# Mechanical.net
KiCad netlist of a schematic drawn in Altium Designer
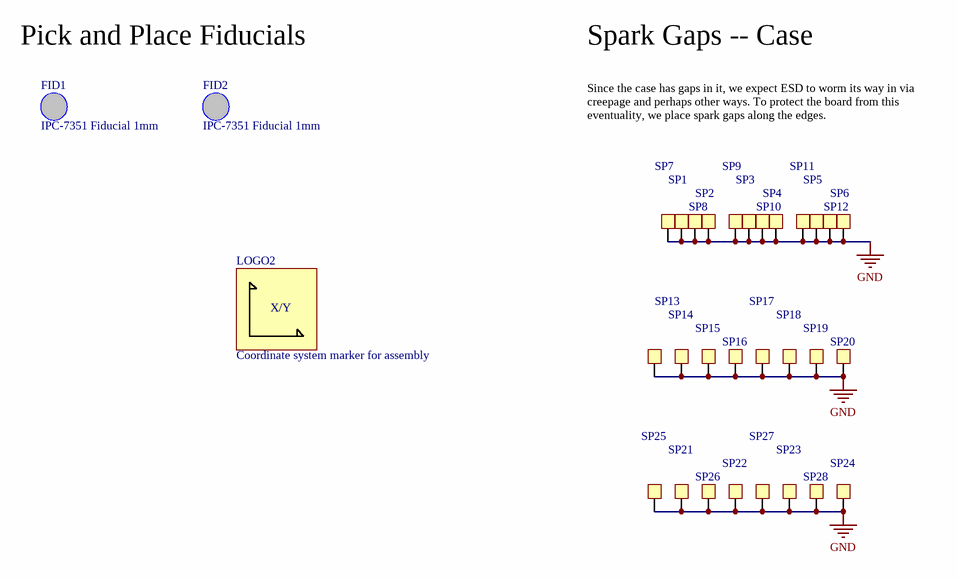
[diagram p0: Mechanical.SchDoc]

(export (version "E")
  (design (tool "Eeschema 10.0.6"))
  (components
    (comp (ref "FID1")
      (value "IPC-7351 Fiducial 1mm")
      (footprint "FIDUCIAL_1.5")
      (libsource (lib "Mechanical") (part "FIDUCIAL_1.5"))
    )
    (comp (ref "FID2")
      (value "IPC-7351 Fiducial 1mm")
      (footprint "FIDUCIAL_1.5")
      (libsource (lib "Mechanical") (part "FIDUCIAL_1.5"))
    )
    (comp (ref "LOGO2")
      (value "Coordinate system marker for assembly")
      (footprint "Coordinate System")
      (libsource (lib "Graphics") (part "CoordinateSystem"))
    )
    (comp (ref "SP1")
      (value "Spark Gap")
      (footprint "SparkGap")
      (description "Open square pad for spark gapping")
      (libsource (lib "PCBFeatures") (part "Spark Gap"))
    )
    (comp (ref "SP2")
      (value "Spark Gap")
      (footprint "SparkGap")
      (description "Open square pad for spark gapping")
      (libsource (lib "PCBFeatures") (part "Spark Gap"))
    )
    (comp (ref "SP3")
      (value "Spark Gap")
      (footprint "SparkGap")
      (description "Open square pad for spark gapping")
      (libsource (lib "PCBFeatures") (part "Spark Gap"))
    )
    (comp (ref "SP4")
      (value "Spark Gap")
      (footprint "SparkGap")
      (description "Open square pad for spark gapping")
      (libsource (lib "PCBFeatures") (part "Spark Gap"))
    )
    (comp (ref "SP5")
      (value "Spark Gap")
      (footprint "SparkGap")
      (description "Open square pad for spark gapping")
      (libsource (lib "PCBFeatures") (part "Spark Gap"))
    )
    (comp (ref "SP6")
      (value "Spark Gap")
      (footprint "SparkGap")
      (description "Open square pad for spark gapping")
      (libsource (lib "PCBFeatures") (part "Spark Gap"))
    )
    (comp (ref "SP7")
      (value "Spark Gap")
      (footprint "SparkGap")
      (description "Open square pad for spark gapping")
      (libsource (lib "PCBFeatures") (part "Spark Gap"))
    )
    (comp (ref "SP8")
      (value "Spark Gap")
      (footprint "SparkGap")
      (description "Open square pad for spark gapping")
      (libsource (lib "PCBFeatures") (part "Spark Gap"))
    )
    (comp (ref "SP9")
      (value "Spark Gap")
      (footprint "SparkGap")
      (description "Open square pad for spark gapping")
      (libsource (lib "PCBFeatures") (part "Spark Gap"))
    )
    (comp (ref "SP10")
      (value "Spark Gap")
      (footprint "SparkGap")
      (description "Open square pad for spark gapping")
      (libsource (lib "PCBFeatures") (part "Spark Gap"))
    )
    (comp (ref "SP11")
      (value "Spark Gap")
      (footprint "SparkGap")
      (description "Open square pad for spark gapping")
      (libsource (lib "PCBFeatures") (part "Spark Gap"))
    )
    (comp (ref "SP12")
      (value "Spark Gap")
      (footprint "SparkGap")
      (description "Open square pad for spark gapping")
      (libsource (lib "PCBFeatures") (part "Spark Gap"))
    )
    (comp (ref "SP13")
      (value "Spark Gap")
      (footprint "SparkGap")
      (description "Open square pad for spark gapping")
      (libsource (lib "PCBFeatures") (part "Spark Gap"))
    )
    (comp (ref "SP14")
      (value "Spark Gap")
      (footprint "SparkGap")
      (description "Open square pad for spark gapping")
      (libsource (lib "PCBFeatures") (part "Spark Gap"))
    )
    (comp (ref "SP15")
      (value "Spark Gap")
      (footprint "SparkGap")
      (description "Open square pad for spark gapping")
      (libsource (lib "PCBFeatures") (part "Spark Gap"))
    )
    (comp (ref "SP16")
      (value "Spark Gap")
      (footprint "SparkGap")
      (description "Open square pad for spark gapping")
      (libsource (lib "PCBFeatures") (part "Spark Gap"))
    )
    (comp (ref "SP17")
      (value "Spark Gap")
      (footprint "SparkGap")
      (description "Open square pad for spark gapping")
      (libsource (lib "PCBFeatures") (part "Spark Gap"))
    )
    (comp (ref "SP18")
      (value "Spark Gap")
      (footprint "SparkGap")
      (description "Open square pad for spark gapping")
      (libsource (lib "PCBFeatures") (part "Spark Gap"))
    )
    (comp (ref "SP19")
      (value "Spark Gap")
      (footprint "SparkGap")
      (description "Open square pad for spark gapping")
      (libsource (lib "PCBFeatures") (part "Spark Gap"))
    )
    (comp (ref "SP20")
      (value "Spark Gap")
      (footprint "SparkGap")
      (description "Open square pad for spark gapping")
      (libsource (lib "PCBFeatures") (part "Spark Gap"))
    )
    (comp (ref "SP21")
      (value "Spark Gap")
      (footprint "SparkGap")
      (description "Open square pad for spark gapping")
      (libsource (lib "PCBFeatures") (part "Spark Gap"))
    )
    (comp (ref "SP22")
      (value "Spark Gap")
      (footprint "SparkGap")
      (description "Open square pad for spark gapping")
      (libsource (lib "PCBFeatures") (part "Spark Gap"))
    )
    (comp (ref "SP23")
      (value "Spark Gap")
      (footprint "SparkGap")
      (description "Open square pad for spark gapping")
      (libsource (lib "PCBFeatures") (part "Spark Gap"))
    )
    (comp (ref "SP24")
      (value "Spark Gap")
      (footprint "SparkGap")
      (description "Open square pad for spark gapping")
      (libsource (lib "PCBFeatures") (part "Spark Gap"))
    )
    (comp (ref "SP25")
      (value "Spark Gap")
      (footprint "SparkGap")
      (description "Open square pad for spark gapping")
      (libsource (lib "PCBFeatures") (part "Spark Gap"))
    )
    (comp (ref "SP26")
      (value "Spark Gap")
      (footprint "SparkGap")
      (description "Open square pad for spark gapping")
      (libsource (lib "PCBFeatures") (part "Spark Gap"))
    )
    (comp (ref "SP27")
      (value "Spark Gap")
      (footprint "SparkGap")
      (description "Open square pad for spark gapping")
      (libsource (lib "PCBFeatures") (part "Spark Gap"))
    )
    (comp (ref "SP28")
      (value "Spark Gap")
      (footprint "SparkGap")
      (description "Open square pad for spark gapping")
      (libsource (lib "PCBFeatures") (part "Spark Gap"))
    )
  )
  (nets
    (net (code "1") (name "GND") (class "Default")
      (node (ref "SP1") (pin "1") (pinfunction "1_1") (pintype "passive"))
      (node (ref "SP10") (pin "1") (pinfunction "1_1") (pintype "passive"))
      (node (ref "SP11") (pin "1") (pinfunction "1_1") (pintype "passive"))
      (node (ref "SP12") (pin "1") (pinfunction "1_1") (pintype "passive"))
      (node (ref "SP13") (pin "1") (pinfunction "1_1") (pintype "passive"))
      (node (ref "SP14") (pin "1") (pinfunction "1_1") (pintype "passive"))
      (node (ref "SP15") (pin "1") (pinfunction "1_1") (pintype "passive"))
      (node (ref "SP16") (pin "1") (pinfunction "1_1") (pintype "passive"))
      (node (ref "SP17") (pin "1") (pinfunction "1_1") (pintype "passive"))
      (node (ref "SP18") (pin "1") (pinfunction "1_1") (pintype "passive"))
      (node (ref "SP19") (pin "1") (pinfunction "1_1") (pintype "passive"))
      (node (ref "SP2") (pin "1") (pinfunction "1_1") (pintype "passive"))
      (node (ref "SP20") (pin "1") (pinfunction "1_1") (pintype "passive"))
      (node (ref "SP21") (pin "1") (pinfunction "1_1") (pintype "passive"))
      (node (ref "SP22") (pin "1") (pinfunction "1_1") (pintype "passive"))
      (node (ref "SP23") (pin "1") (pinfunction "1_1") (pintype "passive"))
      (node (ref "SP24") (pin "1") (pinfunction "1_1") (pintype "passive"))
      (node (ref "SP25") (pin "1") (pinfunction "1_1") (pintype "passive"))
      (node (ref "SP26") (pin "1") (pinfunction "1_1") (pintype "passive"))
      (node (ref "SP27") (pin "1") (pinfunction "1_1") (pintype "passive"))
      (node (ref "SP28") (pin "1") (pinfunction "1_1") (pintype "passive"))
      (node (ref "SP3") (pin "1") (pinfunction "1_1") (pintype "passive"))
      (node (ref "SP4") (pin "1") (pinfunction "1_1") (pintype "passive"))
      (node (ref "SP5") (pin "1") (pinfunction "1_1") (pintype "passive"))
      (node (ref "SP6") (pin "1") (pinfunction "1_1") (pintype "passive"))
      (node (ref "SP7") (pin "1") (pinfunction "1_1") (pintype "passive"))
      (node (ref "SP8") (pin "1") (pinfunction "1_1") (pintype "passive"))
      (node (ref "SP9") (pin "1") (pinfunction "1_1") (pintype "passive"))
    )
    (net (code "2") (name "unconnected-(FID1-Pad1)") (class "Default")
      (node (ref "FID1") (pin "1") (pinfunction "1_1") (pintype "passive"))
    )
    (net (code "3") (name "unconnected-(FID2-Pad1)") (class "Default")
      (node (ref "FID2") (pin "1") (pinfunction "1_1") (pintype "passive"))
    )
  )
)
